# rfidLock3.net
KiCad netlist of a schematic drawn in EAGLE
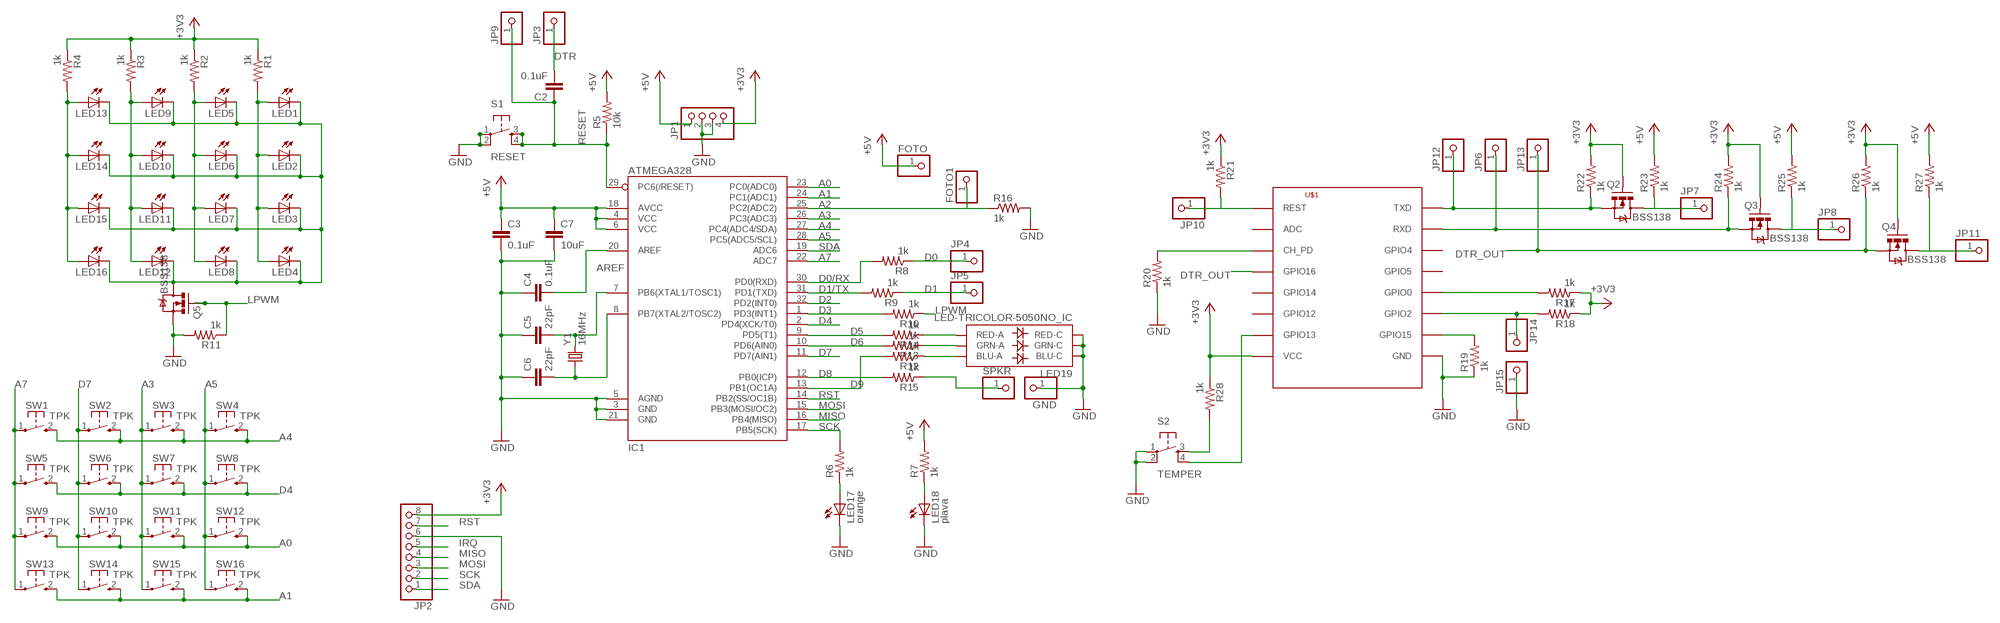
[diagram p0: schematic, sheet 1]

(export (version "E")
  (design (tool "Eeschema 10.0.6"))
  (components
    (comp (ref "C2")
      (value "0.1uF")
      (footprint "eagle-import:0805")
      (libsource (lib "eagle-import") (part "CAP0805"))
    )
    (comp (ref "C3")
      (value "0.1uF")
      (footprint "eagle-import:0805")
      (libsource (lib "eagle-import") (part "CAP0805"))
    )
    (comp (ref "C4")
      (value "0.1uF")
      (footprint "eagle-import:0805")
      (libsource (lib "eagle-import") (part "CAP0805"))
    )
    (comp (ref "C5")
      (value "22pF")
      (footprint "eagle-import:0805")
      (libsource (lib "eagle-import") (part "CAP0805"))
    )
    (comp (ref "C6")
      (value "22pF")
      (footprint "eagle-import:0805")
      (libsource (lib "eagle-import") (part "CAP0805"))
    )
    (comp (ref "C7")
      (value "10uF")
      (footprint "eagle-import:C3216")
      (libsource (lib "eagle-import") (part "C-EUC3216"))
    )
    (comp (ref "FOTO")
      (value "PINHD-1X1")
      (footprint "eagle-import:1X01")
      (libsource (lib "eagle-import") (part "PINHD-1X1"))
    )
    (comp (ref "FOTO1")
      (value "PINHD-1X1")
      (footprint "eagle-import:1X01")
      (libsource (lib "eagle-import") (part "PINHD-1X1"))
    )
    (comp (ref "GND")
      (value "PINHD-1X1")
      (footprint "eagle-import:1X01")
      (libsource (lib "eagle-import") (part "PINHD-1X1"))
    )
    (comp (ref "IC1")
      (value "ATMEGA328")
      (footprint "eagle-import:TQFP32-08")
      (libsource (lib "eagle-import") (part "ATMEGA168"))
    )
    (comp (ref "JP1")
      (value "PINHD-1X4")
      (footprint "eagle-import:1X04")
      (libsource (lib "eagle-import") (part "PINHD-1X4"))
    )
    (comp (ref "JP2")
      (value "PINHD-1X8")
      (footprint "eagle-import:1X08")
      (libsource (lib "eagle-import") (part "PINHD-1X8"))
    )
    (comp (ref "JP3")
      (value "PINHD-1X1")
      (footprint "eagle-import:1X01")
      (libsource (lib "eagle-import") (part "PINHD-1X1"))
    )
    (comp (ref "JP4")
      (value "PINHD-1X1")
      (footprint "eagle-import:1X01")
      (libsource (lib "eagle-import") (part "PINHD-1X1"))
    )
    (comp (ref "JP5")
      (value "PINHD-1X1")
      (footprint "eagle-import:1X01")
      (libsource (lib "eagle-import") (part "PINHD-1X1"))
    )
    (comp (ref "JP6")
      (value "PINHD-1X1")
      (footprint "eagle-import:1X01")
      (libsource (lib "eagle-import") (part "PINHD-1X1"))
    )
    (comp (ref "JP7")
      (value "PINHD-1X1")
      (footprint "eagle-import:1X01")
      (libsource (lib "eagle-import") (part "PINHD-1X1"))
    )
    (comp (ref "JP8")
      (value "PINHD-1X1")
      (footprint "eagle-import:1X01")
      (libsource (lib "eagle-import") (part "PINHD-1X1"))
    )
    (comp (ref "JP9")
      (value "PINHD-1X1")
      (footprint "eagle-import:1X01")
      (libsource (lib "eagle-import") (part "PINHD-1X1"))
    )
    (comp (ref "JP10")
      (value "PINHD-1X1")
      (footprint "eagle-import:1X01")
      (libsource (lib "eagle-import") (part "PINHD-1X1"))
    )
    (comp (ref "JP11")
      (value "PINHD-1X1")
      (footprint "eagle-import:1X01")
      (libsource (lib "eagle-import") (part "PINHD-1X1"))
    )
    (comp (ref "JP12")
      (value "PINHD-1X1")
      (footprint "eagle-import:1X01")
      (libsource (lib "eagle-import") (part "PINHD-1X1"))
    )
    (comp (ref "JP13")
      (value "PINHD-1X1")
      (footprint "eagle-import:1X01")
      (libsource (lib "eagle-import") (part "PINHD-1X1"))
    )
    (comp (ref "JP14")
      (value "PINHD-1X1")
      (footprint "eagle-import:1X01")
      (libsource (lib "eagle-import") (part "PINHD-1X1"))
    )
    (comp (ref "JP15")
      (value "PINHD-1X1")
      (footprint "eagle-import:1X01")
      (libsource (lib "eagle-import") (part "PINHD-1X1"))
    )
    (comp (ref "LED1")
      (value "LED_E")
      (footprint "eagle-import:LED_1206")
      (libsource (lib "eagle-import") (part "LED_E"))
    )
    (comp (ref "LED2")
      (value "LED_E")
      (footprint "eagle-import:LED_1206")
      (libsource (lib "eagle-import") (part "LED_E"))
    )
    (comp (ref "LED3")
      (value "LED_E")
      (footprint "eagle-import:LED_1206")
      (libsource (lib "eagle-import") (part "LED_E"))
    )
    (comp (ref "LED4")
      (value "LED_E")
      (footprint "eagle-import:LED_1206")
      (libsource (lib "eagle-import") (part "LED_E"))
    )
    (comp (ref "LED5")
      (value "LED_E")
      (footprint "eagle-import:LED_1206")
      (libsource (lib "eagle-import") (part "LED_E"))
    )
    (comp (ref "LED6")
      (value "LED_E")
      (footprint "eagle-import:LED_1206")
      (libsource (lib "eagle-import") (part "LED_E"))
    )
    (comp (ref "LED7")
      (value "LED_E")
      (footprint "eagle-import:LED_1206")
      (libsource (lib "eagle-import") (part "LED_E"))
    )
    (comp (ref "LED8")
      (value "LED_E")
      (footprint "eagle-import:LED_1206")
      (libsource (lib "eagle-import") (part "LED_E"))
    )
    (comp (ref "LED9")
      (value "LED_E")
      (footprint "eagle-import:LED_1206")
      (libsource (lib "eagle-import") (part "LED_E"))
    )
    (comp (ref "LED10")
      (value "LED_E")
      (footprint "eagle-import:LED_1206")
      (libsource (lib "eagle-import") (part "LED_E"))
    )
    (comp (ref "LED11")
      (value "LED_E")
      (footprint "eagle-import:LED_1206")
      (libsource (lib "eagle-import") (part "LED_E"))
    )
    (comp (ref "LED12")
      (value "LED_E")
      (footprint "eagle-import:LED_1206")
      (libsource (lib "eagle-import") (part "LED_E"))
    )
    (comp (ref "LED13")
      (value "LED_E")
      (footprint "eagle-import:LED_1206")
      (libsource (lib "eagle-import") (part "LED_E"))
    )
    (comp (ref "LED14")
      (value "LED_E")
      (footprint "eagle-import:LED_1206")
      (libsource (lib "eagle-import") (part "LED_E"))
    )
    (comp (ref "LED15")
      (value "LED_E")
      (footprint "eagle-import:LED_1206")
      (libsource (lib "eagle-import") (part "LED_E"))
    )
    (comp (ref "LED16")
      (value "LED_E")
      (footprint "eagle-import:LED_1206")
      (libsource (lib "eagle-import") (part "LED_E"))
    )
    (comp (ref "LED17")
      (value "orange")
      (footprint "eagle-import:CHIP-LED0805")
      (libsource (lib "eagle-import") (part "LEDCHIP-LED0805"))
    )
    (comp (ref "LED18")
      (value "plava")
      (footprint "eagle-import:CHIP-LED0805")
      (libsource (lib "eagle-import") (part "LEDCHIP-LED0805"))
    )
    (comp (ref "LED19")
      (value "LED-TRICOLOR-5050NO_IC")
      (footprint "eagle-import:LED-TRICOLOR-5050")
      (libsource (lib "eagle-import") (part "LED-TRICOLOR-5050NO_IC"))
    )
    (comp (ref "Q2")
      (value "BSS138")
      (footprint "eagle-import:SOT23-3")
      (libsource (lib "eagle-import") (part "MOSFET-NCHANNELSMD"))
    )
    (comp (ref "Q3")
      (value "BSS138")
      (footprint "eagle-import:SOT23-3")
      (libsource (lib "eagle-import") (part "MOSFET-NCHANNELSMD"))
    )
    (comp (ref "Q4")
      (value "BSS138")
      (footprint "eagle-import:SOT23-3")
      (libsource (lib "eagle-import") (part "MOSFET-NCHANNELSMD"))
    )
    (comp (ref "Q5")
      (value "BSS138")
      (footprint "eagle-import:SOT23-3")
      (libsource (lib "eagle-import") (part "MOSFET-NCHANNELSMD"))
    )
    (comp (ref "R1")
      (value "1k")
      (footprint "eagle-import:0805")
      (libsource (lib "eagle-import") (part "RESISTOR0805-RES"))
    )
    (comp (ref "R2")
      (value "1k")
      (footprint "eagle-import:0805")
      (libsource (lib "eagle-import") (part "RESISTOR0805-RES"))
    )
    (comp (ref "R3")
      (value "1k")
      (footprint "eagle-import:0805")
      (libsource (lib "eagle-import") (part "RESISTOR0805-RES"))
    )
    (comp (ref "R4")
      (value "1k")
      (footprint "eagle-import:0805")
      (libsource (lib "eagle-import") (part "RESISTOR0805-RES"))
    )
    (comp (ref "R5")
      (value "10k")
      (footprint "eagle-import:0805")
      (libsource (lib "eagle-import") (part "RESISTOR0805-RES"))
    )
    (comp (ref "R6")
      (value "1k")
      (footprint "eagle-import:0805")
      (libsource (lib "eagle-import") (part "RESISTOR0805-RES"))
    )
    (comp (ref "R7")
      (value "1k")
      (footprint "eagle-import:0805")
      (libsource (lib "eagle-import") (part "RESISTOR0805-RES"))
    )
    (comp (ref "R8")
      (value "1k")
      (footprint "eagle-import:0805")
      (libsource (lib "eagle-import") (part "RESISTOR0805-RES"))
    )
    (comp (ref "R9")
      (value "1k")
      (footprint "eagle-import:0805")
      (libsource (lib "eagle-import") (part "RESISTOR0805-RES"))
    )
    (comp (ref "R10")
      (value "1k")
      (footprint "eagle-import:0805")
      (libsource (lib "eagle-import") (part "RESISTOR0805-RES"))
    )
    (comp (ref "R11")
      (value "1k")
      (footprint "eagle-import:0805")
      (libsource (lib "eagle-import") (part "RESISTOR0805-RES"))
    )
    (comp (ref "R12")
      (value "1k")
      (footprint "eagle-import:0805")
      (libsource (lib "eagle-import") (part "RESISTOR0805-RES"))
    )
    (comp (ref "R13")
      (value "1k")
      (footprint "eagle-import:0805")
      (libsource (lib "eagle-import") (part "RESISTOR0805-RES"))
    )
    (comp (ref "R14")
      (value "1k")
      (footprint "eagle-import:0805")
      (libsource (lib "eagle-import") (part "RESISTOR0805-RES"))
    )
    (comp (ref "R15")
      (value "1k")
      (footprint "eagle-import:0805")
      (libsource (lib "eagle-import") (part "RESISTOR0805-RES"))
    )
    (comp (ref "R16")
      (value "1k")
      (footprint "eagle-import:0805")
      (libsource (lib "eagle-import") (part "RESISTOR0805-RES"))
    )
    (comp (ref "R17")
      (value "1k")
      (footprint "eagle-import:0805")
      (libsource (lib "eagle-import") (part "RESISTOR0805-RES"))
    )
    (comp (ref "R18")
      (value "1k")
      (footprint "eagle-import:0805")
      (libsource (lib "eagle-import") (part "RESISTOR0805-RES"))
    )
    (comp (ref "R19")
      (value "1k")
      (footprint "eagle-import:0805")
      (libsource (lib "eagle-import") (part "RESISTOR0805-RES"))
    )
    (comp (ref "R20")
      (value "1k")
      (footprint "eagle-import:0805")
      (libsource (lib "eagle-import") (part "RESISTOR0805-RES"))
    )
    (comp (ref "R21")
      (value "1k")
      (footprint "eagle-import:0805")
      (libsource (lib "eagle-import") (part "RESISTOR0805-RES"))
    )
    (comp (ref "R22")
      (value "1k")
      (footprint "eagle-import:0805")
      (libsource (lib "eagle-import") (part "RESISTOR0805-RES"))
    )
    (comp (ref "R23")
      (value "1k")
      (footprint "eagle-import:0805")
      (libsource (lib "eagle-import") (part "RESISTOR0805-RES"))
    )
    (comp (ref "R24")
      (value "1k")
      (footprint "eagle-import:0805")
      (libsource (lib "eagle-import") (part "RESISTOR0805-RES"))
    )
    (comp (ref "R25")
      (value "1k")
      (footprint "eagle-import:0805")
      (libsource (lib "eagle-import") (part "RESISTOR0805-RES"))
    )
    (comp (ref "R26")
      (value "1k")
      (footprint "eagle-import:0805")
      (libsource (lib "eagle-import") (part "RESISTOR0805-RES"))
    )
    (comp (ref "R27")
      (value "1k")
      (footprint "eagle-import:0805")
      (libsource (lib "eagle-import") (part "RESISTOR0805-RES"))
    )
    (comp (ref "R28")
      (value "1k")
      (footprint "eagle-import:0805")
      (libsource (lib "eagle-import") (part "RESISTOR0805-RES"))
    )
    (comp (ref "S1")
      (value "RESET")
      (footprint "eagle-import:TACTILE_SWITCH_SMD")
      (libsource (lib "eagle-import") (part "TAC_SWITCHSMD"))
    )
    (comp (ref "S2")
      (value "TEMPER")
      (footprint "eagle-import:TACTILE_SWITCH_SMD")
      (libsource (lib "eagle-import") (part "TAC_SWITCHSMD"))
    )
    (comp (ref "SPKR")
      (value "PINHD-1X1")
      (footprint "eagle-import:1X01")
      (libsource (lib "eagle-import") (part "PINHD-1X1"))
    )
    (comp (ref "SW1")
      (value "TPK")
      (footprint "eagle-import:KSS-2EG4430")
      (libsource (lib "eagle-import") (part "KSS-2EG4430"))
    )
    (comp (ref "SW2")
      (value "TPK")
      (footprint "eagle-import:KSS-2EG4430")
      (libsource (lib "eagle-import") (part "KSS-2EG4430"))
    )
    (comp (ref "SW3")
      (value "TPK")
      (footprint "eagle-import:KSS-2EG4430")
      (libsource (lib "eagle-import") (part "KSS-2EG4430"))
    )
    (comp (ref "SW4")
      (value "TPK")
      (footprint "eagle-import:KSS-2EG4430")
      (libsource (lib "eagle-import") (part "KSS-2EG4430"))
    )
    (comp (ref "SW5")
      (value "TPK")
      (footprint "eagle-import:KSS-2EG4430")
      (libsource (lib "eagle-import") (part "KSS-2EG4430"))
    )
    (comp (ref "SW6")
      (value "TPK")
      (footprint "eagle-import:KSS-2EG4430")
      (libsource (lib "eagle-import") (part "KSS-2EG4430"))
    )
    (comp (ref "SW7")
      (value "TPK")
      (footprint "eagle-import:KSS-2EG4430")
      (libsource (lib "eagle-import") (part "KSS-2EG4430"))
    )
    (comp (ref "SW8")
      (value "TPK")
      (footprint "eagle-import:KSS-2EG4430")
      (libsource (lib "eagle-import") (part "KSS-2EG4430"))
    )
    (comp (ref "SW9")
      (value "TPK")
      (footprint "eagle-import:KSS-2EG4430")
      (libsource (lib "eagle-import") (part "KSS-2EG4430"))
    )
    (comp (ref "SW10")
      (value "TPK")
      (footprint "eagle-import:KSS-2EG4430")
      (libsource (lib "eagle-import") (part "KSS-2EG4430"))
    )
    (comp (ref "SW11")
      (value "TPK")
      (footprint "eagle-import:KSS-2EG4430")
      (libsource (lib "eagle-import") (part "KSS-2EG4430"))
    )
    (comp (ref "SW12")
      (value "TPK")
      (footprint "eagle-import:KSS-2EG4430")
      (libsource (lib "eagle-import") (part "KSS-2EG4430"))
    )
    (comp (ref "SW13")
      (value "TPK")
      (footprint "eagle-import:KSS-2EG4430")
      (libsource (lib "eagle-import") (part "KSS-2EG4430"))
    )
    (comp (ref "SW14")
      (value "TPK")
      (footprint "eagle-import:KSS-2EG4430")
      (libsource (lib "eagle-import") (part "KSS-2EG4430"))
    )
    (comp (ref "SW15")
      (value "TPK")
      (footprint "eagle-import:KSS-2EG4430")
      (libsource (lib "eagle-import") (part "KSS-2EG4430"))
    )
    (comp (ref "SW16")
      (value "TPK")
      (footprint "eagle-import:KSS-2EG4430")
      (libsource (lib "eagle-import") (part "KSS-2EG4430"))
    )
    (comp (ref "U$1")
      (value "ESP8266-07")
      (footprint "eagle-import:ESP-07")
      (libsource (lib "eagle-import") (part "ESP8266-07"))
    )
    (comp (ref "Y1")
      (value "16MHz")
      (footprint "eagle-import:CRYSTAL-SMD-5X3")
      (libsource (lib "eagle-import") (part "CRYSTAL5X3"))
    )
  )
  (nets
    (net (code "1") (name "+3V3") (class "Default")
      (node (ref "JP1") (pin "4") (pinfunction "4_4") (pintype "passive"))
      (node (ref "JP2") (pin "8") (pinfunction "8_8") (pintype "passive"))
      (node (ref "Q2") (pin "1") (pinfunction "G_1") (pintype "passive"))
      (node (ref "Q3") (pin "1") (pinfunction "G_1") (pintype "passive"))
      (node (ref "Q4") (pin "1") (pinfunction "G_1") (pintype "passive"))
      (node (ref "R1") (pin "1") (pinfunction "1_1") (pintype "passive"))
      (node (ref "R17") (pin "1") (pinfunction "1_1") (pintype "passive"))
      (node (ref "R18") (pin "1") (pinfunction "1_1") (pintype "passive"))
      (node (ref "R2") (pin "1") (pinfunction "1_1") (pintype "passive"))
      (node (ref "R21") (pin "1") (pinfunction "1_1") (pintype "passive"))
      (node (ref "R22") (pin "2") (pinfunction "2_2") (pintype "passive"))
      (node (ref "R24") (pin "2") (pinfunction "2_2") (pintype "passive"))
      (node (ref "R26") (pin "2") (pinfunction "2_2") (pintype "passive"))
      (node (ref "R28") (pin "1") (pinfunction "1_1") (pintype "passive"))
      (node (ref "R3") (pin "1") (pinfunction "1_1") (pintype "passive"))
      (node (ref "R4") (pin "1") (pinfunction "1_1") (pintype "passive"))
      (node (ref "U$1") (pin "VCC") (pinfunction "VCC_VCC") (pintype "power_in"))
    )
    (net (code "2") (name "+5V") (class "Default")
      (node (ref "C3") (pin "1") (pinfunction "1_1") (pintype "passive"))
      (node (ref "C7") (pin "1") (pinfunction "1_1") (pintype "passive"))
      (node (ref "FOTO") (pin "1") (pinfunction "1_1") (pintype "passive"))
      (node (ref "IC1") (pin "18") (pinfunction "AVCC_18") (pintype "bidirectional"))
      (node (ref "IC1") (pin "4") (pinfunction "VCC_4") (pintype "bidirectional"))
      (node (ref "IC1") (pin "6") (pinfunction "VCC_6") (pintype "bidirectional"))
      (node (ref "JP1") (pin "1") (pinfunction "1_1") (pintype "passive"))
      (node (ref "R23") (pin "2") (pinfunction "2_2") (pintype "passive"))
      (node (ref "R25") (pin "2") (pinfunction "2_2") (pintype "passive"))
      (node (ref "R27") (pin "2") (pinfunction "2_2") (pintype "passive"))
      (node (ref "R5") (pin "2") (pinfunction "2_2") (pintype "passive"))
      (node (ref "R7") (pin "2") (pinfunction "2_2") (pintype "passive"))
    )
    (net (code "3") (name "/A0") (class "Default")
      (node (ref "IC1") (pin "23") (pinfunction "PC0(ADC0)_23") (pintype "bidirectional"))
      (node (ref "SW10") (pin "2") (pinfunction "S_2") (pintype "passive"))
      (node (ref "SW11") (pin "2") (pinfunction "S_2") (pintype "passive"))
      (node (ref "SW12") (pin "2") (pinfunction "S_2") (pintype "passive"))
      (node (ref "SW9") (pin "2") (pinfunction "S_2") (pintype "passive"))
    )
    (net (code "4") (name "/A1") (class "Default")
      (node (ref "IC1") (pin "24") (pinfunction "PC1(ADC1)_24") (pintype "bidirectional"))
      (node (ref "SW13") (pin "2") (pinfunction "S_2") (pintype "passive"))
      (node (ref "SW14") (pin "2") (pinfunction "S_2") (pintype "passive"))
      (node (ref "SW15") (pin "2") (pinfunction "S_2") (pintype "passive"))
      (node (ref "SW16") (pin "2") (pinfunction "S_2") (pintype "passive"))
    )
    (net (code "5") (name "/A2") (class "Default")
      (node (ref "FOTO1") (pin "1") (pinfunction "1_1") (pintype "passive"))
      (node (ref "IC1") (pin "25") (pinfunction "PC2(ADC2)_25") (pintype "bidirectional"))
      (node (ref "R16") (pin "1") (pinfunction "1_1") (pintype "passive"))
    )
    (net (code "6") (name "/A3") (class "Default")
      (node (ref "IC1") (pin "26") (pinfunction "PC3(ADC3)_26") (pintype "bidirectional"))
      (node (ref "SW11") (pin "1") (pinfunction "P_1") (pintype "passive"))
      (node (ref "SW15") (pin "1") (pinfunction "P_1") (pintype "passive"))
      (node (ref "SW3") (pin "1") (pinfunction "P_1") (pintype "passive"))
      (node (ref "SW7") (pin "1") (pinfunction "P_1") (pintype "passive"))
    )
    (net (code "7") (name "/A4") (class "Default")
      (node (ref "IC1") (pin "27") (pinfunction "PC4(ADC4/SDA)_27") (pintype "bidirectional"))
      (node (ref "SW1") (pin "2") (pinfunction "S_2") (pintype "passive"))
      (node (ref "SW2") (pin "2") (pinfunction "S_2") (pintype "passive"))
      (node (ref "SW3") (pin "2") (pinfunction "S_2") (pintype "passive"))
      (node (ref "SW4") (pin "2") (pinfunction "S_2") (pintype "passive"))
    )
    (net (code "8") (name "/A5") (class "Default")
      (node (ref "IC1") (pin "28") (pinfunction "PC5(ADC5/SCL)_28") (pintype "bidirectional"))
      (node (ref "SW12") (pin "1") (pinfunction "P_1") (pintype "passive"))
      (node (ref "SW16") (pin "1") (pinfunction "P_1") (pintype "passive"))
      (node (ref "SW4") (pin "1") (pinfunction "P_1") (pintype "passive"))
      (node (ref "SW8") (pin "1") (pinfunction "P_1") (pintype "passive"))
    )
    (net (code "9") (name "/A7") (class "Default")
      (node (ref "IC1") (pin "22") (pinfunction "ADC7_22") (pintype "bidirectional"))
      (node (ref "SW1") (pin "1") (pinfunction "P_1") (pintype "passive"))
      (node (ref "SW13") (pin "1") (pinfunction "P_1") (pintype "passive"))
      (node (ref "SW5") (pin "1") (pinfunction "P_1") (pintype "passive"))
      (node (ref "SW9") (pin "1") (pinfunction "P_1") (pintype "passive"))
    )
    (net (code "10") (name "/AREF") (class "Default")
      (node (ref "C4") (pin "2") (pinfunction "2_2") (pintype "passive"))
      (node (ref "IC1") (pin "20") (pinfunction "AREF_20") (pintype "bidirectional"))
    )
    (net (code "11") (name "/D0") (class "Default")
      (node (ref "JP4") (pin "1") (pinfunction "1_1") (pintype "passive"))
      (node (ref "R8") (pin "1") (pinfunction "1_1") (pintype "passive"))
    )
    (net (code "12") (name "/D0{slash}RX") (class "Default")
      (node (ref "IC1") (pin "30") (pinfunction "PD0(RXD)_30") (pintype "bidirectional"))
      (node (ref "R8") (pin "2") (pinfunction "2_2") (pintype "passive"))
    )
    (net (code "13") (name "/D1") (class "Default")
      (node (ref "JP5") (pin "1") (pinfunction "1_1") (pintype "passive"))
      (node (ref "R9") (pin "1") (pinfunction "1_1") (pintype "passive"))
    )
    (net (code "14") (name "/D1{slash}TX") (class "Default")
      (node (ref "IC1") (pin "31") (pinfunction "PD1(TXD)_31") (pintype "bidirectional"))
      (node (ref "R9") (pin "2") (pinfunction "2_2") (pintype "passive"))
    )
    (net (code "15") (name "/D2") (class "Default")
      (node (ref "IC1") (pin "32") (pinfunction "PD2(INT0)_32") (pintype "bidirectional"))
    )
    (net (code "16") (name "/D3") (class "Default")
      (node (ref "IC1") (pin "1") (pinfunction "PD3(INT1)_1") (pintype "bidirectional"))
      (node (ref "R10") (pin "2") (pinfunction "2_2") (pintype "passive"))
    )
    (net (code "17") (name "/D4") (class "Default")
      (node (ref "IC1") (pin "2") (pinfunction "PD4(XCK/T0)_2") (pintype "bidirectional"))
      (node (ref "SW5") (pin "2") (pinfunction "S_2") (pintype "passive"))
      (node (ref "SW6") (pin "2") (pinfunction "S_2") (pintype "passive"))
      (node (ref "SW7") (pin "2") (pinfunction "S_2") (pintype "passive"))
      (node (ref "SW8") (pin "2") (pinfunction "S_2") (pintype "passive"))
    )
    (net (code "18") (name "/D5") (class "Default")
      (node (ref "IC1") (pin "9") (pinfunction "PD5(T1)_9") (pintype "bidirectional"))
      (node (ref "R14") (pin "2") (pinfunction "2_2") (pintype "passive"))
    )
    (net (code "19") (name "/D6") (class "Default")
      (node (ref "IC1") (pin "10") (pinfunction "PD6(AIN0)_10") (pintype "bidirectional"))
      (node (ref "R13") (pin "2") (pinfunction "2_2") (pintype "passive"))
    )
    (net (code "20") (name "/D7") (class "Default")
      (node (ref "IC1") (pin "11") (pinfunction "PD7(AIN1)_11") (pintype "bidirectional"))
      (node (ref "SW10") (pin "1") (pinfunction "P_1") (pintype "passive"))
      (node (ref "SW14") (pin "1") (pinfunction "P_1") (pintype "passive"))
      (node (ref "SW2") (pin "1") (pinfunction "P_1") (pintype "passive"))
      (node (ref "SW6") (pin "1") (pinfunction "P_1") (pintype "passive"))
    )
    (net (code "21") (name "/D8") (class "Default")
      (node (ref "IC1") (pin "12") (pinfunction "PB0(ICP)_12") (pintype "bidirectional"))
      (node (ref "R15") (pin "2") (pinfunction "2_2") (pintype "passive"))
    )
    (net (code "22") (name "/D9") (class "Default")
      (node (ref "IC1") (pin "13") (pinfunction "PB1(OC1A)_13") (pintype "bidirectional"))
      (node (ref "R12") (pin "2") (pinfunction "2_2") (pintype "passive"))
    )
    (net (code "23") (name "/DTR") (class "Default")
      (node (ref "C2") (pin "2") (pinfunction "2_2") (pintype "passive"))
      (node (ref "JP3") (pin "1") (pinfunction "1_1") (pintype "passive"))
    )
    (net (code "24") (name "/DTR_OUT") (class "Default")
      (node (ref "JP13") (pin "1") (pinfunction "1_1") (pintype "passive"))
      (node (ref "Q4") (pin "2") (pinfunction "S_2") (pintype "passive"))
      (node (ref "R26") (pin "1") (pinfunction "1_1") (pintype "passive"))
      (node (ref "U$1") (pin "GPIO16") (pinfunction "GPIO16_GPIO16") (pintype "bidirectional"))
    )
    (net (code "25") (name "/IRQ") (class "Default")
      (node (ref "JP2") (pin "5") (pinfunction "5_5") (pintype "passive"))
    )
    (net (code "26") (name "/LPWM") (class "Default")
      (node (ref "Q5") (pin "1") (pinfunction "G_1") (pintype "passive"))
      (node (ref "R10") (pin "1") (pinfunction "1_1") (pintype "passive"))
      (node (ref "R11") (pin "1") (pinfunction "1_1") (pintype "passive"))
    )
    (net (code "27") (name "/MISO") (class "Default")
      (node (ref "IC1") (pin "16") (pinfunction "PB4(MISO)_16") (pintype "bidirectional"))
      (node (ref "JP2") (pin "4") (pinfunction "4_4") (pintype "passive"))
    )
    (net (code "28") (name "/MOSI") (class "Default")
      (node (ref "IC1") (pin "15") (pinfunction "PB3(MOSI/OC2)_15") (pintype "bidirectional"))
      (node (ref "JP2") (pin "3") (pinfunction "3_3") (pintype "passive"))
    )
    (net (code "29") (name "/RESET") (class "Default")
      (node (ref "C2") (pin "1") (pinfunction "1_1") (pintype "passive"))
      (node (ref "IC1") (pin "29") (pinfunction "PC6(/RESET)_29") (pintype "bidirectional"))
      (node (ref "JP9") (pin "1") (pinfunction "1_1") (pintype "passive"))
      (node (ref "R5") (pin "1") (pinfunction "1_1") (pintype "passive"))
      (node (ref "S1") (pin "3") (pinfunction "3_3") (pintype "passive"))
      (node (ref "S1") (pin "4") (pinfunction "4_4") (pintype "passive"))
    )
    (net (code "30") (name "/RST") (class "Default")
      (node (ref "IC1") (pin "14") (pinfunction "PB2(SS/OC1B)_14") (pintype "bidirectional"))
      (node (ref "JP2") (pin "7") (pinfunction "7_7") (pintype "passive"))
    )
    (net (code "31") (name "/SCK") (class "Default")
      (node (ref "IC1") (pin "17") (pinfunction "PB5(SCK)_17") (pintype "bidirectional"))
      (node (ref "JP2") (pin "2") (pinfunction "2_2") (pintype "passive"))
      (node (ref "R6") (pin "2") (pinfunction "2_2") (pintype "passive"))
    )
    (net (code "32") (name "/SDA") (class "Default")
      (node (ref "IC1") (pin "19") (pinfunction "ADC6_19") (pintype "bidirectional"))
      (node (ref "JP2") (pin "1") (pinfunction "1_1") (pintype "passive"))
    )
    (net (code "33") (name "GND") (class "Default")
      (node (ref "C3") (pin "2") (pinfunction "2_2") (pintype "passive"))
      (node (ref "C4") (pin "1") (pinfunction "1_1") (pintype "passive"))
      (node (ref "C5") (pin "1") (pinfunction "1_1") (pintype "passive"))
      (node (ref "C6") (pin "1") (pinfunction "1_1") (pintype "passive"))
      (node (ref "C7") (pin "2") (pinfunction "2_2") (pintype "passive"))
      (node (ref "GND") (pin "1") (pinfunction "1_1") (pintype "passive"))
      (node (ref "IC1") (pin "21") (pinfunction "GND_21") (pintype "bidirectional"))
      (node (ref "IC1") (pin "3") (pinfunction "GND_3") (pintype "bidirectional"))
      (node (ref "IC1") (pin "5") (pinfunction "AGND_5") (pintype "bidirectional"))
      (node (ref "JP1") (pin "2") (pinfunction "2_2") (pintype "passive"))
      (node (ref "JP1") (pin "3") (pinfunction "3_3") (pintype "passive"))
      (node (ref "JP15") (pin "1") (pinfunction "1_1") (pintype "passive"))
      (node (ref "JP2") (pin "6") (pinfunction "6_6") (pintype "passive"))
      (node (ref "LED17") (pin "C") (pinfunction "C_C") (pintype "passive"))
      (node (ref "LED18") (pin "C") (pinfunction "C_C") (pintype "passive"))
      (node (ref "LED19") (pin "4") (pinfunction "BLU-C_4") (pintype "bidirectional"))
      (node (ref "LED19") (pin "5") (pinfunction "RED-C_5") (pintype "bidirectional"))
      (node (ref "LED19") (pin "6") (pinfunction "GRN-C_6") (pintype "bidirectional"))
      (node (ref "Q5") (pin "2") (pinfunction "S_2") (pintype "passive"))
      (node (ref "R11") (pin "2") (pinfunction "2_2") (pintype "passive"))
      (node (ref "R16") (pin "2") (pinfunction "2_2") (pintype "passive"))
      (node (ref "R19") (pin "1") (pinfunction "1_1") (pintype "passive"))
      (node (ref "R20") (pin "1") (pinfunction "1_1") (pintype "passive"))
      (node (ref "S1") (pin "1") (pinfunction "1_1") (pintype "passive"))
      (node (ref "S1") (pin "2") (pinfunction "2_2") (pintype "passive"))
      (node (ref "S2") (pin "1") (pinfunction "1_1") (pintype "passive"))
      (node (ref "S2") (pin "2") (pinfunction "2_2") (pintype "passive"))
      (node (ref "U$1") (pin "GND") (pinfunction "GND_GND") (pintype "power_in"))
    )
    (net (code "34") (name "Net-(IC1-PB6(XTAL1{slash}TOSC1))") (class "Default")
      (node (ref "C5") (pin "2") (pinfunction "2_2") (pintype "passive"))
      (node (ref "IC1") (pin "7") (pinfunction "PB6(XTAL1/TOSC1)_7") (pintype "bidirectional"))
      (node (ref "Y1") (pin "3") (pinfunction "2_3") (pintype "passive"))
    )
    (net (code "35") (name "Net-(IC1-PB7(XTAL2{slash}TOSC2))") (class "Default")
      (node (ref "C6") (pin "2") (pinfunction "2_2") (pintype "passive"))
      (node (ref "IC1") (pin "8") (pinfunction "PB7(XTAL2/TOSC2)_8") (pintype "bidirectional"))
      (node (ref "Y1") (pin "1") (pinfunction "1_1") (pintype "passive"))
    )
    (net (code "36") (name "Net-(JP10-Pad1)") (class "Default")
      (node (ref "JP10") (pin "1") (pinfunction "1_1") (pintype "passive"))
      (node (ref "R21") (pin "2") (pinfunction "2_2") (pintype "passive"))
      (node (ref "U$1") (pin "REST") (pinfunction "REST_REST") (pintype "bidirectional"))
    )
    (net (code "37") (name "Net-(JP14-Pad1)") (class "Default")
      (node (ref "JP14") (pin "1") (pinfunction "1_1") (pintype "passive"))
      (node (ref "R18") (pin "2") (pinfunction "2_2") (pintype "passive"))
      (node (ref "U$1") (pin "GPIO2") (pinfunction "GPIO2_GPIO2") (pintype "bidirectional"))
    )
    (net (code "38") (name "Net-(LED1-PadA)") (class "Default")
      (node (ref "LED1") (pin "A") (pinfunction "A_A") (pintype "passive"))
      (node (ref "LED2") (pin "A") (pinfunction "A_A") (pintype "passive"))
      (node (ref "LED3") (pin "A") (pinfunction "A_A") (pintype "passive"))
      (node (ref "LED4") (pin "A") (pinfunction "A_A") (pintype "passive"))
      (node (ref "R1") (pin "2") (pinfunction "2_2") (pintype "passive"))
    )
    (net (code "39") (name "Net-(LED5-PadA)") (class "Default")
      (node (ref "LED5") (pin "A") (pinfunction "A_A") (pintype "passive"))
      (node (ref "LED6") (pin "A") (pinfunction "A_A") (pintype "passive"))
      (node (ref "LED7") (pin "A") (pinfunction "A_A") (pintype "passive"))
      (node (ref "LED8") (pin "A") (pinfunction "A_A") (pintype "passive"))
      (node (ref "R2") (pin "2") (pinfunction "2_2") (pintype "passive"))
    )
    (net (code "40") (name "Net-(LED10-PadA)") (class "Default")
      (node (ref "LED10") (pin "A") (pinfunction "A_A") (pintype "passive"))
      (node (ref "LED11") (pin "A") (pinfunction "A_A") (pintype "passive"))
      (node (ref "LED12") (pin "A") (pinfunction "A_A") (pintype "passive"))
      (node (ref "LED9") (pin "A") (pinfunction "A_A") (pintype "passive"))
      (node (ref "R3") (pin "2") (pinfunction "2_2") (pintype "passive"))
    )
    (net (code "41") (name "Net-(LED13-PadA)") (class "Default")
      (node (ref "LED13") (pin "A") (pinfunction "A_A") (pintype "passive"))
      (node (ref "LED14") (pin "A") (pinfunction "A_A") (pintype "passive"))
      (node (ref "LED15") (pin "A") (pinfunction "A_A") (pintype "passive"))
      (node (ref "LED16") (pin "A") (pinfunction "A_A") (pintype "passive"))
      (node (ref "R4") (pin "2") (pinfunction "2_2") (pintype "passive"))
    )
    (net (code "42") (name "Net-(LED17-PadA)") (class "Default")
      (node (ref "LED17") (pin "A") (pinfunction "A_A") (pintype "passive"))
      (node (ref "R6") (pin "1") (pinfunction "1_1") (pintype "passive"))
    )
    (net (code "43") (name "Net-(LED18-PadA)") (class "Default")
      (node (ref "LED18") (pin "A") (pinfunction "A_A") (pintype "passive"))
      (node (ref "R7") (pin "1") (pinfunction "1_1") (pintype "passive"))
    )
    (net (code "44") (name "Net-(LED19-BLU-A)") (class "Default")
      (node (ref "LED19") (pin "3") (pinfunction "BLU-A_3") (pintype "bidirectional"))
      (node (ref "R12") (pin "1") (pinfunction "1_1") (pintype "passive"))
    )
    (net (code "45") (name "Net-(LED19-GRN-A)") (class "Default")
      (node (ref "LED19") (pin "1") (pinfunction "GRN-A_1") (pintype "bidirectional"))
      (node (ref "R13") (pin "1") (pinfunction "1_1") (pintype "passive"))
    )
    (net (code "46") (name "Net-(LED19-RED-A)") (class "Default")
      (node (ref "LED19") (pin "2") (pinfunction "RED-A_2") (pintype "bidirectional"))
      (node (ref "R14") (pin "1") (pinfunction "1_1") (pintype "passive"))
    )
    (net (code "47") (name "Net-(Q2-D)") (class "Default")
      (node (ref "JP7") (pin "1") (pinfunction "1_1") (pintype "passive"))
      (node (ref "Q2") (pin "3") (pinfunction "D_3") (pintype "passive"))
      (node (ref "R23") (pin "1") (pinfunction "1_1") (pintype "passive"))
    )
    (net (code "48") (name "Net-(Q2-S)") (class "Default")
      (node (ref "JP12") (pin "1") (pinfunction "1_1") (pintype "passive"))
      (node (ref "Q2") (pin "2") (pinfunction "S_2") (pintype "passive"))
      (node (ref "R22") (pin "1") (pinfunction "1_1") (pintype "passive"))
      (node (ref "U$1") (pin "TXD") (pinfunction "TXD_TXD") (pintype "output"))
    )
    (net (code "49") (name "Net-(Q3-D)") (class "Default")
      (node (ref "JP8") (pin "1") (pinfunction "1_1") (pintype "passive"))
      (node (ref "Q3") (pin "3") (pinfunction "D_3") (pintype "passive"))
      (node (ref "R25") (pin "1") (pinfunction "1_1") (pintype "passive"))
    )
    (net (code "50") (name "Net-(Q3-S)") (class "Default")
      (node (ref "JP6") (pin "1") (pinfunction "1_1") (pintype "passive"))
      (node (ref "Q3") (pin "2") (pinfunction "S_2") (pintype "passive"))
      (node (ref "R24") (pin "1") (pinfunction "1_1") (pintype "passive"))
      (node (ref "U$1") (pin "RXD") (pinfunction "RXD_RXD") (pintype "input"))
    )
    (net (code "51") (name "Net-(Q4-D)") (class "Default")
      (node (ref "JP11") (pin "1") (pinfunction "1_1") (pintype "passive"))
      (node (ref "Q4") (pin "3") (pinfunction "D_3") (pintype "passive"))
      (node (ref "R27") (pin "1") (pinfunction "1_1") (pintype "passive"))
    )
    (net (code "52") (name "Net-(Q5-D)") (class "Default")
      (node (ref "LED1") (pin "C") (pinfunction "C_C") (pintype "passive"))
      (node (ref "LED10") (pin "C") (pinfunction "C_C") (pintype "passive"))
      (node (ref "LED11") (pin "C") (pinfunction "C_C") (pintype "passive"))
      (node (ref "LED12") (pin "C") (pinfunction "C_C") (pintype "passive"))
      (node (ref "LED13") (pin "C") (pinfunction "C_C") (pintype "passive"))
      (node (ref "LED14") (pin "C") (pinfunction "C_C") (pintype "passive"))
      (node (ref "LED15") (pin "C") (pinfunction "C_C") (pintype "passive"))
      (node (ref "LED16") (pin "C") (pinfunction "C_C") (pintype "passive"))
      (node (ref "LED2") (pin "C") (pinfunction "C_C") (pintype "passive"))
      (node (ref "LED3") (pin "C") (pinfunction "C_C") (pintype "passive"))
      (node (ref "LED4") (pin "C") (pinfunction "C_C") (pintype "passive"))
      (node (ref "LED5") (pin "C") (pinfunction "C_C") (pintype "passive"))
      (node (ref "LED6") (pin "C") (pinfunction "C_C") (pintype "passive"))
      (node (ref "LED7") (pin "C") (pinfunction "C_C") (pintype "passive"))
      (node (ref "LED8") (pin "C") (pinfunction "C_C") (pintype "passive"))
      (node (ref "LED9") (pin "C") (pinfunction "C_C") (pintype "passive"))
      (node (ref "Q5") (pin "3") (pinfunction "D_3") (pintype "passive"))
    )
    (net (code "53") (name "Net-(R15-Pad1)") (class "Default")
      (node (ref "R15") (pin "1") (pinfunction "1_1") (pintype "passive"))
      (node (ref "SPKR") (pin "1") (pinfunction "1_1") (pintype "passive"))
    )
    (net (code "54") (name "Net-(R17-Pad2)") (class "Default")
      (node (ref "R17") (pin "2") (pinfunction "2_2") (pintype "passive"))
      (node (ref "U$1") (pin "GPIO0") (pinfunction "GPIO0_GPIO0") (pintype "bidirectional"))
    )
    (net (code "55") (name "Net-(R19-Pad2)") (class "Default")
      (node (ref "R19") (pin "2") (pinfunction "2_2") (pintype "passive"))
      (node (ref "U$1") (pin "GPIO15") (pinfunction "GPIO15_GPIO15") (pintype "input"))
    )
    (net (code "56") (name "Net-(R20-Pad2)") (class "Default")
      (node (ref "R20") (pin "2") (pinfunction "2_2") (pintype "passive"))
      (node (ref "U$1") (pin "CH_PD") (pinfunction "CH_PD_CH_PD") (pintype "input"))
    )
    (net (code "57") (name "Net-(R28-Pad2)") (class "Default")
      (node (ref "R28") (pin "2") (pinfunction "2_2") (pintype "passive"))
      (node (ref "S2") (pin "3") (pinfunction "3_3") (pintype "passive"))
    )
    (net (code "58") (name "Net-(S2-Pad4)") (class "Default")
      (node (ref "S2") (pin "4") (pinfunction "4_4") (pintype "passive"))
      (node (ref "U$1") (pin "GPIO13") (pinfunction "GPIO13_GPIO13") (pintype "bidirectional"))
    )
    (net (code "59") (name "unconnected-(U$1-PadADC)") (class "Default")
      (node (ref "U$1") (pin "ADC") (pinfunction "ADC_ADC") (pintype "bidirectional"))
    )
    (net (code "60") (name "unconnected-(U$1-PadGPIO4)") (class "Default")
      (node (ref "U$1") (pin "GPIO4") (pinfunction "GPIO4_GPIO4") (pintype "bidirectional"))
    )
    (net (code "61") (name "unconnected-(U$1-PadGPIO5)") (class "Default")
      (node (ref "U$1") (pin "GPIO5") (pinfunction "GPIO5_GPIO5") (pintype "bidirectional"))
    )
    (net (code "62") (name "unconnected-(U$1-PadGPIO12)") (class "Default")
      (node (ref "U$1") (pin "GPIO12") (pinfunction "GPIO12_GPIO12") (pintype "bidirectional"))
    )
    (net (code "63") (name "unconnected-(U$1-PadGPIO14)") (class "Default")
      (node (ref "U$1") (pin "GPIO14") (pinfunction "GPIO14_GPIO14") (pintype "bidirectional"))
    )
  )
)
